# Engine_Room.net
KiCad netlist of a schematic drawn in EAGLE
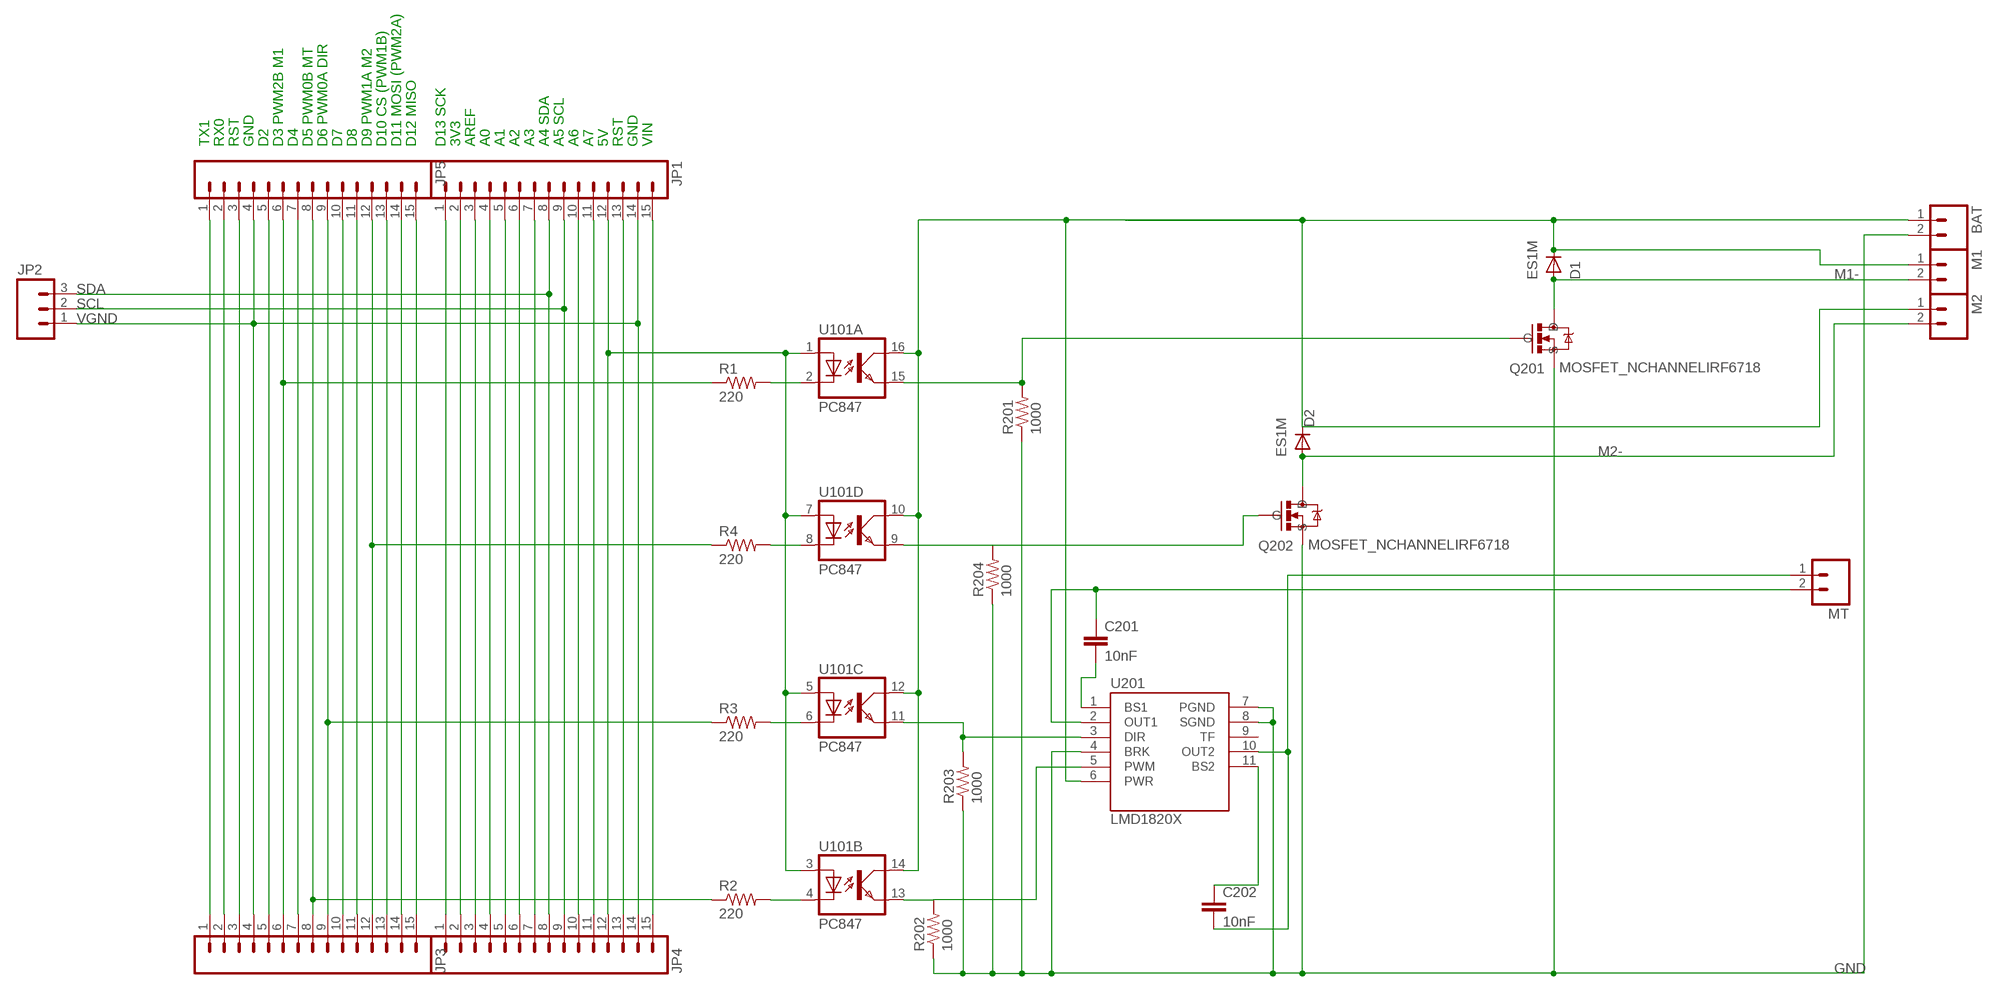
[diagram p0: schematic, sheet 1]

(export (version "E")
  (design (tool "Eeschema 10.0.6"))
  (components
    (comp (ref "BAT")
      (value "M02PTH4")
      (footprint "eagle-import:1X02_XTRA_BIG")
      (libsource (lib "eagle-import") (part "M02PTH4"))
    )
    (comp (ref "C201")
      (value "10nF")
      (footprint "eagle-import:0402-CAP")
      (libsource (lib "eagle-import") (part "CAP0402-CAP"))
    )
    (comp (ref "C202")
      (value "10nF")
      (footprint "eagle-import:0402-CAP")
      (libsource (lib "eagle-import") (part "CAP0402-CAP"))
    )
    (comp (ref "D1")
      (value "ES1M")
      (footprint "eagle-import:DO-214AC")
      (libsource (lib "eagle-import") (part "DIODE-DO-214AC"))
    )
    (comp (ref "D2")
      (value "ES1M")
      (footprint "eagle-import:DO-214AC")
      (libsource (lib "eagle-import") (part "DIODE-DO-214AC"))
    )
    (comp (ref "JP1")
      (value "M15LOCK")
      (footprint "eagle-import:1X15_LOCK")
      (libsource (lib "eagle-import") (part "M15LOCK"))
    )
    (comp (ref "JP2")
      (value "M03LOCK")
      (footprint "eagle-import:1X03_LOCK")
      (libsource (lib "eagle-import") (part "M03LOCK"))
    )
    (comp (ref "JP3")
      (value "M15")
      (footprint "eagle-import:1X15")
      (libsource (lib "eagle-import") (part "M15"))
    )
    (comp (ref "JP4")
      (value "M15")
      (footprint "eagle-import:1X15")
      (libsource (lib "eagle-import") (part "M15"))
    )
    (comp (ref "JP5")
      (value "M15LOCK")
      (footprint "eagle-import:1X15_LOCK")
      (libsource (lib "eagle-import") (part "M15LOCK"))
    )
    (comp (ref "M1")
      (value "M02PTH4")
      (footprint "eagle-import:1X02_XTRA_BIG")
      (libsource (lib "eagle-import") (part "M02PTH4"))
    )
    (comp (ref "M2")
      (value "M02PTH4")
      (footprint "eagle-import:1X02_XTRA_BIG")
      (libsource (lib "eagle-import") (part "M02PTH4"))
    )
    (comp (ref "MT")
      (value "M02PTH")
      (footprint "eagle-import:1X02")
      (libsource (lib "eagle-import") (part "M02PTH"))
    )
    (comp (ref "Q201")
      (value "MOSFET_NCHANNELIRF6718")
      (footprint "eagle-import:DIRECTFET_L6")
      (libsource (lib "eagle-import") (part "MOSFET_NCHANNELIRF6718"))
    )
    (comp (ref "Q202")
      (value "MOSFET_NCHANNELIRF6718")
      (footprint "eagle-import:DIRECTFET_L6")
      (libsource (lib "eagle-import") (part "MOSFET_NCHANNELIRF6718"))
    )
    (comp (ref "R1")
      (value "220")
      (footprint "eagle-import:0402-RES")
      (libsource (lib "eagle-import") (part "RESISTOR0402-RES"))
    )
    (comp (ref "R2")
      (value "220")
      (footprint "eagle-import:0402-RES")
      (libsource (lib "eagle-import") (part "RESISTOR0402-RES"))
    )
    (comp (ref "R3")
      (value "220")
      (footprint "eagle-import:0402-RES")
      (libsource (lib "eagle-import") (part "RESISTOR0402-RES"))
    )
    (comp (ref "R4")
      (value "220")
      (footprint "eagle-import:0402-RES")
      (libsource (lib "eagle-import") (part "RESISTOR0402-RES"))
    )
    (comp (ref "R201")
      (value "1000")
      (footprint "eagle-import:0402-RES")
      (libsource (lib "eagle-import") (part "RESISTOR0402-RES"))
    )
    (comp (ref "R202")
      (value "1000")
      (footprint "eagle-import:0402-RES")
      (libsource (lib "eagle-import") (part "RESISTOR0402-RES"))
    )
    (comp (ref "R203")
      (value "1000")
      (footprint "eagle-import:0402-RES")
      (libsource (lib "eagle-import") (part "RESISTOR0402-RES"))
    )
    (comp (ref "R204")
      (value "1000")
      (footprint "eagle-import:0402-RES")
      (libsource (lib "eagle-import") (part "RESISTOR0402-RES"))
    )
    (comp (ref "U101")
      (value "PC847")
      (footprint "eagle-import:DIL16")
      (libsource (lib "eagle-import") (part "PC847"))
    )
    (comp (ref "U201")
      (value "LMD1820X")
      (footprint "eagle-import:TO-220-11LEAD")
      (libsource (lib "eagle-import") (part "LMD1820X"))
    )
  )
  (nets
    (net (code "1") (name "/GND") (class "Default")
      (node (ref "BAT") (pin "2") (pinfunction "2_2") (pintype "passive"))
      (node (ref "Q201") (pin "S") (pinfunction "S_S") (pintype "passive"))
      (node (ref "Q202") (pin "S") (pinfunction "S_S") (pintype "passive"))
      (node (ref "R201") (pin "1") (pinfunction "1_1") (pintype "passive"))
      (node (ref "R202") (pin "1") (pinfunction "1_1") (pintype "passive"))
      (node (ref "R203") (pin "1") (pinfunction "1_1") (pintype "passive"))
      (node (ref "R204") (pin "1") (pinfunction "1_1") (pintype "passive"))
      (node (ref "U201") (pin "4") (pinfunction "BRK_4") (pintype "bidirectional"))
      (node (ref "U201") (pin "7") (pinfunction "PGND_7") (pintype "bidirectional"))
      (node (ref "U201") (pin "8") (pinfunction "SGND_8") (pintype "bidirectional"))
    )
    (net (code "2") (name "/M1-") (class "Default")
      (node (ref "D1") (pin "A") (pinfunction "A_A") (pintype "passive"))
      (node (ref "M1") (pin "2") (pinfunction "2_2") (pintype "passive"))
      (node (ref "Q201") (pin "D1") (pinfunction "D_D1") (pintype "passive"))
      (node (ref "Q201") (pin "D2") (pinfunction "D_D2") (pintype "passive"))
    )
    (net (code "3") (name "/M2-") (class "Default")
      (node (ref "D2") (pin "A") (pinfunction "A_A") (pintype "passive"))
      (node (ref "M2") (pin "2") (pinfunction "2_2") (pintype "passive"))
      (node (ref "Q202") (pin "D1") (pinfunction "D_D1") (pintype "passive"))
      (node (ref "Q202") (pin "D2") (pinfunction "D_D2") (pintype "passive"))
    )
    (net (code "4") (name "/SCL") (class "Default")
      (node (ref "JP1") (pin "9") (pinfunction "9_9") (pintype "passive"))
      (node (ref "JP2") (pin "2") (pinfunction "2_2") (pintype "passive"))
      (node (ref "JP4") (pin "9") (pinfunction "9_9") (pintype "passive"))
    )
    (net (code "5") (name "/SDA") (class "Default")
      (node (ref "JP1") (pin "8") (pinfunction "8_8") (pintype "passive"))
      (node (ref "JP2") (pin "3") (pinfunction "3_3") (pintype "passive"))
      (node (ref "JP4") (pin "8") (pinfunction "8_8") (pintype "passive"))
    )
    (net (code "6") (name "/VGND") (class "Default")
      (node (ref "JP1") (pin "14") (pinfunction "14_14") (pintype "passive"))
      (node (ref "JP2") (pin "1") (pinfunction "1_1") (pintype "passive"))
      (node (ref "JP3") (pin "4") (pinfunction "4_4") (pintype "passive"))
      (node (ref "JP4") (pin "14") (pinfunction "14_14") (pintype "passive"))
      (node (ref "JP5") (pin "4") (pinfunction "4_4") (pintype "passive"))
    )
    (net (code "7") (name "Net-(JP1-Pad1)") (class "Default")
      (node (ref "JP1") (pin "1") (pinfunction "1_1") (pintype "passive"))
      (node (ref "JP4") (pin "1") (pinfunction "1_1") (pintype "passive"))
    )
    (net (code "8") (name "Net-(JP1-Pad2)") (class "Default")
      (node (ref "JP1") (pin "2") (pinfunction "2_2") (pintype "passive"))
      (node (ref "JP4") (pin "2") (pinfunction "2_2") (pintype "passive"))
    )
    (net (code "9") (name "Net-(JP1-Pad3)") (class "Default")
      (node (ref "JP1") (pin "3") (pinfunction "3_3") (pintype "passive"))
      (node (ref "JP4") (pin "3") (pinfunction "3_3") (pintype "passive"))
    )
    (net (code "10") (name "Net-(JP1-Pad4)") (class "Default")
      (node (ref "JP1") (pin "4") (pinfunction "4_4") (pintype "passive"))
      (node (ref "JP4") (pin "4") (pinfunction "4_4") (pintype "passive"))
    )
    (net (code "11") (name "Net-(JP1-Pad5)") (class "Default")
      (node (ref "JP1") (pin "5") (pinfunction "5_5") (pintype "passive"))
      (node (ref "JP4") (pin "5") (pinfunction "5_5") (pintype "passive"))
    )
    (net (code "12") (name "Net-(JP1-Pad6)") (class "Default")
      (node (ref "JP1") (pin "6") (pinfunction "6_6") (pintype "passive"))
      (node (ref "JP4") (pin "6") (pinfunction "6_6") (pintype "passive"))
    )
    (net (code "13") (name "Net-(JP1-Pad7)") (class "Default")
      (node (ref "JP1") (pin "7") (pinfunction "7_7") (pintype "passive"))
      (node (ref "JP4") (pin "7") (pinfunction "7_7") (pintype "passive"))
    )
    (net (code "14") (name "Net-(JP1-Pad10)") (class "Default")
      (node (ref "JP1") (pin "10") (pinfunction "10_10") (pintype "passive"))
      (node (ref "JP4") (pin "10") (pinfunction "10_10") (pintype "passive"))
    )
    (net (code "15") (name "Net-(JP1-Pad11)") (class "Default")
      (node (ref "JP1") (pin "11") (pinfunction "11_11") (pintype "passive"))
      (node (ref "JP4") (pin "11") (pinfunction "11_11") (pintype "passive"))
    )
    (net (code "16") (name "Net-(JP1-Pad13)") (class "Default")
      (node (ref "JP1") (pin "13") (pinfunction "13_13") (pintype "passive"))
      (node (ref "JP4") (pin "13") (pinfunction "13_13") (pintype "passive"))
    )
    (net (code "17") (name "Net-(JP1-Pad15)") (class "Default")
      (node (ref "JP1") (pin "15") (pinfunction "15_15") (pintype "passive"))
      (node (ref "JP4") (pin "15") (pinfunction "15_15") (pintype "passive"))
    )
    (net (code "18") (name "Net-(JP3-Pad1)") (class "Default")
      (node (ref "JP3") (pin "1") (pinfunction "1_1") (pintype "passive"))
      (node (ref "JP5") (pin "1") (pinfunction "1_1") (pintype "passive"))
    )
    (net (code "19") (name "Net-(JP3-Pad2)") (class "Default")
      (node (ref "JP3") (pin "2") (pinfunction "2_2") (pintype "passive"))
      (node (ref "JP5") (pin "2") (pinfunction "2_2") (pintype "passive"))
    )
    (net (code "20") (name "Net-(JP3-Pad3)") (class "Default")
      (node (ref "JP3") (pin "3") (pinfunction "3_3") (pintype "passive"))
      (node (ref "JP5") (pin "3") (pinfunction "3_3") (pintype "passive"))
    )
    (net (code "21") (name "Net-(JP3-Pad5)") (class "Default")
      (node (ref "JP3") (pin "5") (pinfunction "5_5") (pintype "passive"))
      (node (ref "JP5") (pin "5") (pinfunction "5_5") (pintype "passive"))
    )
    (net (code "22") (name "Net-(JP3-Pad6)") (class "Default")
      (node (ref "JP3") (pin "6") (pinfunction "6_6") (pintype "passive"))
      (node (ref "JP5") (pin "6") (pinfunction "6_6") (pintype "passive"))
      (node (ref "R1") (pin "1") (pinfunction "1_1") (pintype "passive"))
    )
    (net (code "23") (name "Net-(JP3-Pad7)") (class "Default")
      (node (ref "JP3") (pin "7") (pinfunction "7_7") (pintype "passive"))
      (node (ref "JP5") (pin "7") (pinfunction "7_7") (pintype "passive"))
    )
    (net (code "24") (name "Net-(JP3-Pad8)") (class "Default")
      (node (ref "JP3") (pin "8") (pinfunction "8_8") (pintype "passive"))
      (node (ref "JP5") (pin "8") (pinfunction "8_8") (pintype "passive"))
      (node (ref "R2") (pin "1") (pinfunction "1_1") (pintype "passive"))
    )
    (net (code "25") (name "Net-(JP3-Pad9)") (class "Default")
      (node (ref "JP3") (pin "9") (pinfunction "9_9") (pintype "passive"))
      (node (ref "JP5") (pin "9") (pinfunction "9_9") (pintype "passive"))
      (node (ref "R3") (pin "1") (pinfunction "1_1") (pintype "passive"))
    )
    (net (code "26") (name "Net-(JP3-Pad10)") (class "Default")
      (node (ref "JP3") (pin "10") (pinfunction "10_10") (pintype "passive"))
      (node (ref "JP5") (pin "10") (pinfunction "10_10") (pintype "passive"))
    )
    (net (code "27") (name "Net-(JP3-Pad11)") (class "Default")
      (node (ref "JP3") (pin "11") (pinfunction "11_11") (pintype "passive"))
      (node (ref "JP5") (pin "11") (pinfunction "11_11") (pintype "passive"))
    )
    (net (code "28") (name "Net-(JP3-Pad12)") (class "Default")
      (node (ref "JP3") (pin "12") (pinfunction "12_12") (pintype "passive"))
      (node (ref "JP5") (pin "12") (pinfunction "12_12") (pintype "passive"))
      (node (ref "R4") (pin "1") (pinfunction "1_1") (pintype "passive"))
    )
    (net (code "29") (name "Net-(JP3-Pad13)") (class "Default")
      (node (ref "JP3") (pin "13") (pinfunction "13_13") (pintype "passive"))
      (node (ref "JP5") (pin "13") (pinfunction "13_13") (pintype "passive"))
    )
    (net (code "30") (name "Net-(JP3-Pad14)") (class "Default")
      (node (ref "JP3") (pin "14") (pinfunction "14_14") (pintype "passive"))
      (node (ref "JP5") (pin "14") (pinfunction "14_14") (pintype "passive"))
    )
    (net (code "31") (name "Net-(JP3-Pad15)") (class "Default")
      (node (ref "JP3") (pin "15") (pinfunction "15_15") (pintype "passive"))
      (node (ref "JP5") (pin "15") (pinfunction "15_15") (pintype "passive"))
    )
    (net (code "32") (name "Net-(U101A-A)") (class "Default")
      (node (ref "JP1") (pin "12") (pinfunction "12_12") (pintype "passive"))
      (node (ref "JP4") (pin "12") (pinfunction "12_12") (pintype "passive"))
      (node (ref "U101") (pin "1") (pinfunction "A_1") (pintype "passive"))
      (node (ref "U101") (pin "3") (pinfunction "A_3") (pintype "passive"))
      (node (ref "U101") (pin "5") (pinfunction "A_5") (pintype "passive"))
      (node (ref "U101") (pin "7") (pinfunction "A_7") (pintype "passive"))
    )
    (net (code "33") (name "Net-(U101A-C)") (class "Default")
      (node (ref "R1") (pin "2") (pinfunction "2_2") (pintype "passive"))
      (node (ref "U101") (pin "2") (pinfunction "C_2") (pintype "passive"))
    )
    (net (code "34") (name "Net-(U101A-COL)") (class "Default")
      (node (ref "BAT") (pin "1") (pinfunction "1_1") (pintype "passive"))
      (node (ref "D1") (pin "C") (pinfunction "C_C") (pintype "passive"))
      (node (ref "D2") (pin "C") (pinfunction "C_C") (pintype "passive"))
      (node (ref "M1") (pin "1") (pinfunction "1_1") (pintype "passive"))
      (node (ref "M2") (pin "1") (pinfunction "1_1") (pintype "passive"))
      (node (ref "U101") (pin "10") (pinfunction "COL_10") (pintype "passive"))
      (node (ref "U101") (pin "12") (pinfunction "COL_12") (pintype "passive"))
      (node (ref "U101") (pin "14") (pinfunction "COL_14") (pintype "passive"))
      (node (ref "U101") (pin "16") (pinfunction "COL_16") (pintype "passive"))
      (node (ref "U201") (pin "6") (pinfunction "PWR_6") (pintype "bidirectional"))
    )
    (net (code "35") (name "Net-(U101A-EMIT)") (class "Default")
      (node (ref "Q201") (pin "G") (pinfunction "G_G") (pintype "passive"))
      (node (ref "R201") (pin "2") (pinfunction "2_2") (pintype "passive"))
      (node (ref "U101") (pin "15") (pinfunction "EMIT_15") (pintype "passive"))
    )
    (net (code "36") (name "Net-(U101B-C)") (class "Default")
      (node (ref "R2") (pin "2") (pinfunction "2_2") (pintype "passive"))
      (node (ref "U101") (pin "4") (pinfunction "C_4") (pintype "passive"))
    )
    (net (code "37") (name "Net-(U101B-EMIT)") (class "Default")
      (node (ref "R202") (pin "2") (pinfunction "2_2") (pintype "passive"))
      (node (ref "U101") (pin "13") (pinfunction "EMIT_13") (pintype "passive"))
      (node (ref "U201") (pin "5") (pinfunction "PWM_5") (pintype "bidirectional"))
    )
    (net (code "38") (name "Net-(U101C-C)") (class "Default")
      (node (ref "R3") (pin "2") (pinfunction "2_2") (pintype "passive"))
      (node (ref "U101") (pin "6") (pinfunction "C_6") (pintype "passive"))
    )
    (net (code "39") (name "Net-(U101C-EMIT)") (class "Default")
      (node (ref "R203") (pin "2") (pinfunction "2_2") (pintype "passive"))
      (node (ref "U101") (pin "11") (pinfunction "EMIT_11") (pintype "passive"))
      (node (ref "U201") (pin "3") (pinfunction "DIR_3") (pintype "bidirectional"))
    )
    (net (code "40") (name "Net-(U101D-C)") (class "Default")
      (node (ref "R4") (pin "2") (pinfunction "2_2") (pintype "passive"))
      (node (ref "U101") (pin "8") (pinfunction "C_8") (pintype "passive"))
    )
    (net (code "41") (name "Net-(U101D-EMIT)") (class "Default")
      (node (ref "Q202") (pin "G") (pinfunction "G_G") (pintype "passive"))
      (node (ref "R204") (pin "2") (pinfunction "2_2") (pintype "passive"))
      (node (ref "U101") (pin "9") (pinfunction "EMIT_9") (pintype "passive"))
    )
    (net (code "42") (name "Net-(U201-BS1)") (class "Default")
      (node (ref "C201") (pin "2") (pinfunction "2_2") (pintype "passive"))
      (node (ref "U201") (pin "1") (pinfunction "BS1_1") (pintype "bidirectional"))
    )
    (net (code "43") (name "Net-(U201-BS2)") (class "Default")
      (node (ref "C202") (pin "1") (pinfunction "1_1") (pintype "passive"))
      (node (ref "U201") (pin "11") (pinfunction "BS2_11") (pintype "bidirectional"))
    )
    (net (code "44") (name "Net-(U201-OUT1)") (class "Default")
      (node (ref "C201") (pin "1") (pinfunction "1_1") (pintype "passive"))
      (node (ref "MT") (pin "2") (pinfunction "2_2") (pintype "passive"))
      (node (ref "U201") (pin "2") (pinfunction "OUT1_2") (pintype "bidirectional"))
    )
    (net (code "45") (name "Net-(U201-OUT2)") (class "Default")
      (node (ref "C202") (pin "2") (pinfunction "2_2") (pintype "passive"))
      (node (ref "MT") (pin "1") (pinfunction "1_1") (pintype "passive"))
      (node (ref "U201") (pin "10") (pinfunction "OUT2_10") (pintype "bidirectional"))
    )
    (net (code "46") (name "unconnected-(U201-TF-Pad9)") (class "Default")
      (node (ref "U201") (pin "9") (pinfunction "TF_9") (pintype "bidirectional"))
    )
  )
)
